# Prog_Adaptor.net
KiCad netlist of a schematic drawn in Altium Designer
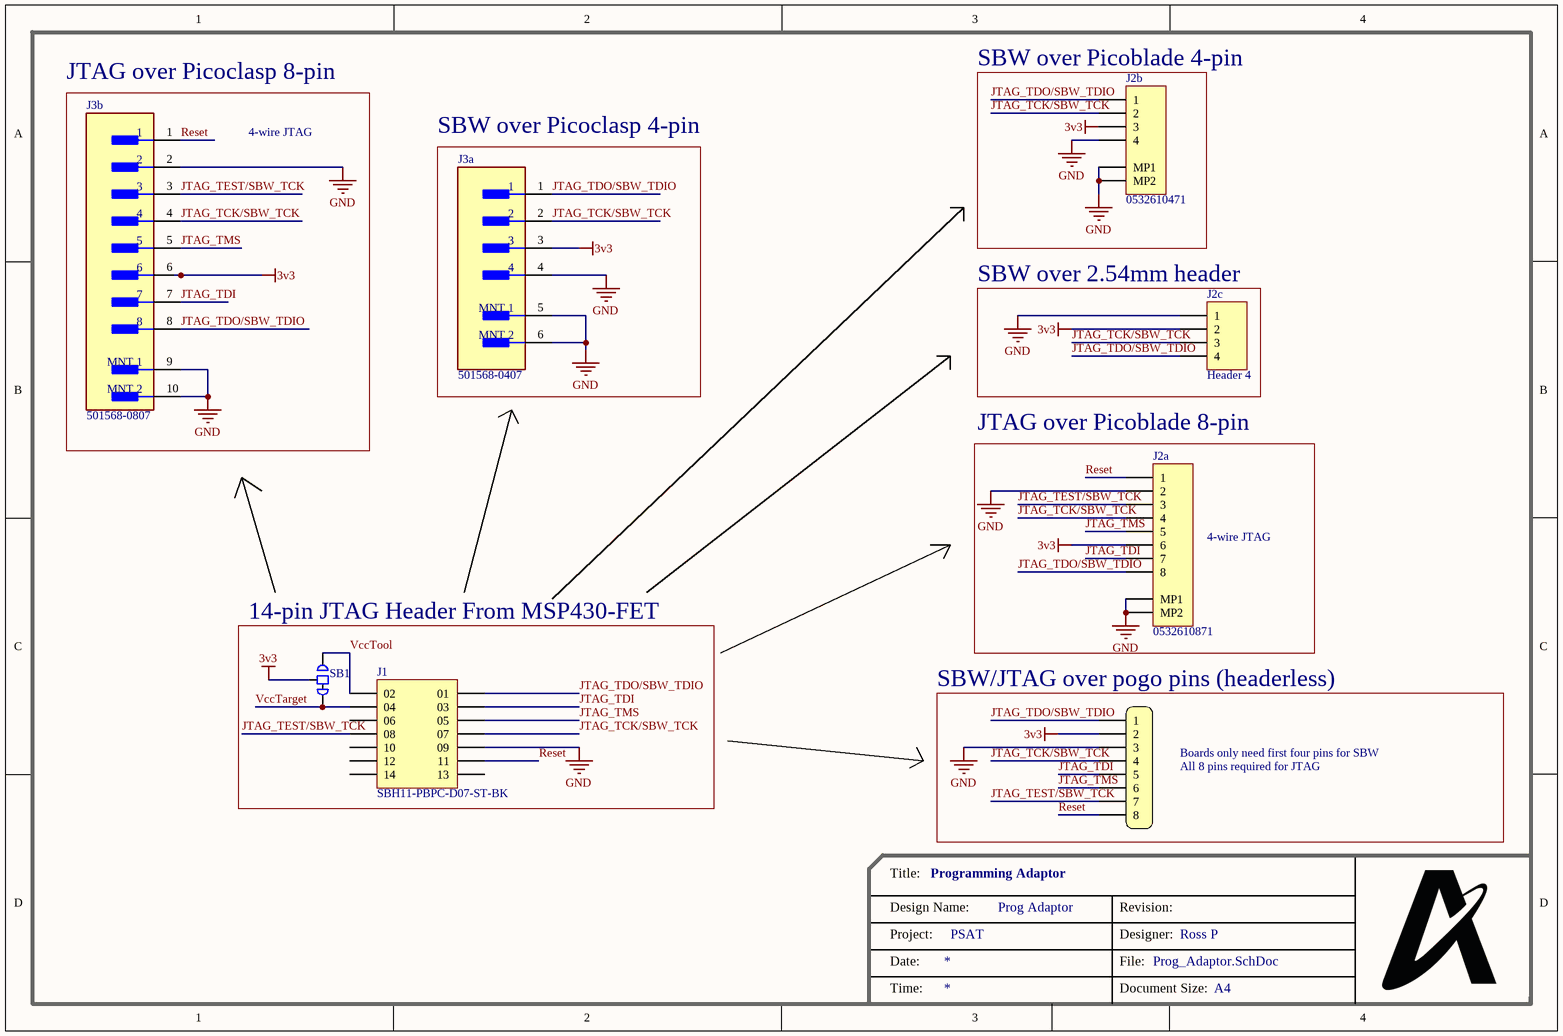
[diagram p0: Prog_Adaptor.SchDoc]

(export (version "E")
  (design (tool "Eeschema 10.0.6"))
  (components
    (comp (ref "J1")
      (value "SBH11-PBPC-D07-ST-BK")
      (footprint "APSS Prototype Parts:SBH11-PBPC-D07-ST-BK")
      (description "14-pin JTAG Male Header")
      (libsource (lib "APSS Prototype Parts") (part "SBH11-PBPC-D07-ST-BK"))
    )
    (comp (ref "J2a")
      (value "0532610871")
      (footprint "APSS Prototype Parts:MOLEX_0532610871")
      (description "Header - Picoblade 08-pin, SMT, RA")
      (fields (field (name "MF PART NO.") "0532610871"))
      (libsource (lib "APSS Prototype Parts") (part "0532610871"))
    )
    (comp (ref "J2b")
      (value "0532610471")
      (footprint "APSS Prototype Parts:MOLEX_0532610471")
      (description "Header - Picoblade 04-pin, SMT, RA")
      (fields (field (name "MF PART NO.") "0532610471"))
      (libsource (lib "APSS Prototype Parts") (part "0532610471"))
    )
    (comp (ref "J2c")
      (value "Header 4")
      (footprint "HDR1X4")
      (description "Header, 4-Pin")
      (fields (field (name "PUBLISHER") "Altium Limited"))
      (libsource (lib "Miscellaneous Connectors") (part "Header 4"))
    )
    (comp (ref "J2d")
      (value "*")
      (footprint "POGO_8_PIN_HEADER")
      (libsource (lib "APSS Generic Components") (part "Headerless Pogo Holes 8-pin"))
    )
    (comp (ref "J3a")
      (value "501568-0407")
      (footprint "FP-501568-0407-MFG")
      (libsource (lib "lonelyjelly84") (part "9ad138ae26d927171cc05ac156b0a09"))
    )
    (comp (ref "J3b")
      (value "501568-0807")
      (footprint "FP-501568-0807-MFG")
      (libsource (lib "lonelyjelly84") (part "c99efc1074d36b7f406f17bfcf6f1d6"))
    )
    (comp (ref "SB1")
      (value "Solder Jumper 3-pin Left connected 0201")
      (footprint "Solder Bridge 3-pin Left shorted 0201")
      (libsource (lib "APSS Generic Components") (part "Solder Jumper 3-pin Normally Closed 0201"))
    )
  )
  (nets
    (net (code "1") (name "/JTAG_TCK{slash}SBW_TCK") (class "Default")
      (node (ref "J1") (pin "07") (pinfunction "07_07") (pintype "passive"))
      (node (ref "J2a") (pin "4") (pinfunction "4_4") (pintype "passive"))
      (node (ref "J2b") (pin "2") (pinfunction "2_2") (pintype "passive"))
      (node (ref "J2c") (pin "3") (pinfunction "3_3") (pintype "passive"))
      (node (ref "J2d") (pin "4") (pinfunction "4_4") (pintype "passive"))
      (node (ref "J3a") (pin "2") (pinfunction "2_2") (pintype "passive"))
      (node (ref "J3b") (pin "4") (pinfunction "4_4") (pintype "passive"))
    )
    (net (code "2") (name "/JTAG_TDI") (class "Default")
      (node (ref "J1") (pin "03") (pinfunction "03_03") (pintype "passive"))
      (node (ref "J2a") (pin "7") (pinfunction "7_7") (pintype "passive"))
      (node (ref "J2d") (pin "5") (pinfunction "5_5") (pintype "passive"))
      (node (ref "J3b") (pin "7") (pinfunction "7_7") (pintype "passive"))
    )
    (net (code "3") (name "/JTAG_TDO{slash}SBW_TDIO") (class "Default")
      (node (ref "J1") (pin "01") (pinfunction "01_01") (pintype "passive"))
      (node (ref "J2a") (pin "8") (pinfunction "8_8") (pintype "passive"))
      (node (ref "J2b") (pin "1") (pinfunction "1_1") (pintype "passive"))
      (node (ref "J2c") (pin "4") (pinfunction "4_4") (pintype "passive"))
      (node (ref "J2d") (pin "1") (pinfunction "1_1") (pintype "passive"))
      (node (ref "J3a") (pin "1") (pinfunction "1_1") (pintype "passive"))
      (node (ref "J3b") (pin "8") (pinfunction "8_8") (pintype "passive"))
    )
    (net (code "4") (name "/JTAG_TEST{slash}SBW_TCK") (class "Default")
      (node (ref "J1") (pin "08") (pinfunction "08_08") (pintype "passive"))
      (node (ref "J2a") (pin "3") (pinfunction "3_3") (pintype "passive"))
      (node (ref "J2d") (pin "7") (pinfunction "7_7") (pintype "passive"))
      (node (ref "J3b") (pin "3") (pinfunction "3_3") (pintype "passive"))
    )
    (net (code "5") (name "/JTAG_TMS") (class "Default")
      (node (ref "J1") (pin "05") (pinfunction "05_05") (pintype "passive"))
      (node (ref "J2a") (pin "5") (pinfunction "5_5") (pintype "passive"))
      (node (ref "J2d") (pin "6") (pinfunction "6_6") (pintype "passive"))
      (node (ref "J3b") (pin "5") (pinfunction "5_5") (pintype "passive"))
    )
    (net (code "6") (name "/Reset") (class "Default")
      (node (ref "J1") (pin "11") (pinfunction "11_11") (pintype "passive"))
      (node (ref "J2a") (pin "1") (pinfunction "1_1") (pintype "passive"))
      (node (ref "J2d") (pin "8") (pinfunction "8_8") (pintype "passive"))
      (node (ref "J3b") (pin "1") (pinfunction "1_1") (pintype "passive"))
    )
    (net (code "7") (name "/VccTarget") (class "Default")
      (node (ref "J1") (pin "04") (pinfunction "04_04") (pintype "passive"))
      (node (ref "SB1") (pin "2") (pinfunction "2_2") (pintype "passive"))
    )
    (net (code "8") (name "/VccTool") (class "Default")
      (node (ref "J1") (pin "02") (pinfunction "02_02") (pintype "passive"))
      (node (ref "SB1") (pin "3") (pinfunction "3_3") (pintype "passive"))
    )
    (net (code "9") (name "3v3") (class "Default")
      (node (ref "J2a") (pin "6") (pinfunction "6_6") (pintype "passive"))
      (node (ref "J2b") (pin "3") (pinfunction "3_3") (pintype "passive"))
      (node (ref "J2c") (pin "2") (pinfunction "2_2") (pintype "passive"))
      (node (ref "J2d") (pin "2") (pinfunction "2_2") (pintype "passive"))
      (node (ref "J3a") (pin "3") (pinfunction "3_3") (pintype "passive"))
      (node (ref "J3b") (pin "6") (pinfunction "6_6") (pintype "passive"))
      (node (ref "SB1") (pin "1") (pinfunction "Common_1") (pintype "passive"))
    )
    (net (code "10") (name "GND") (class "Default")
      (node (ref "J1") (pin "09") (pinfunction "09_09") (pintype "passive"))
      (node (ref "J2a") (pin "2") (pinfunction "2_2") (pintype "passive"))
      (node (ref "J2a") (pin "MP1") (pinfunction "MP1_MP1") (pintype "passive"))
      (node (ref "J2a") (pin "MP2") (pinfunction "MP2_MP2") (pintype "passive"))
      (node (ref "J2b") (pin "4") (pinfunction "4_4") (pintype "passive"))
      (node (ref "J2b") (pin "MP1") (pinfunction "MP1_MP1") (pintype "passive"))
      (node (ref "J2b") (pin "MP2") (pinfunction "MP2_MP2") (pintype "passive"))
      (node (ref "J2c") (pin "1") (pinfunction "1_1") (pintype "passive"))
      (node (ref "J2d") (pin "3") (pinfunction "3_3") (pintype "passive"))
      (node (ref "J3a") (pin "4") (pinfunction "4_4") (pintype "passive"))
      (node (ref "J3a") (pin "5") (pinfunction "MNT_1_5") (pintype "passive"))
      (node (ref "J3a") (pin "6") (pinfunction "MNT_2_6") (pintype "passive"))
      (node (ref "J3b") (pin "10") (pinfunction "MNT_2_10") (pintype "passive"))
      (node (ref "J3b") (pin "2") (pinfunction "2_2") (pintype "passive"))
      (node (ref "J3b") (pin "9") (pinfunction "MNT_1_9") (pintype "passive"))
    )
    (net (code "11") (name "unconnected-(J1-Pad06)") (class "Default")
      (node (ref "J1") (pin "06") (pinfunction "06_06") (pintype "passive"))
    )
    (net (code "12") (name "unconnected-(J1-Pad10)") (class "Default")
      (node (ref "J1") (pin "10") (pinfunction "10_10") (pintype "passive"))
    )
    (net (code "13") (name "unconnected-(J1-Pad12)") (class "Default")
      (node (ref "J1") (pin "12") (pinfunction "12_12") (pintype "passive"))
    )
    (net (code "14") (name "unconnected-(J1-Pad13)") (class "Default")
      (node (ref "J1") (pin "13") (pinfunction "13_13") (pintype "passive"))
    )
    (net (code "15") (name "unconnected-(J1-Pad14)") (class "Default")
      (node (ref "J1") (pin "14") (pinfunction "14_14") (pintype "passive"))
    )
  )
)
